# Screen.net
KiCad netlist of a schematic drawn in Altium Designer
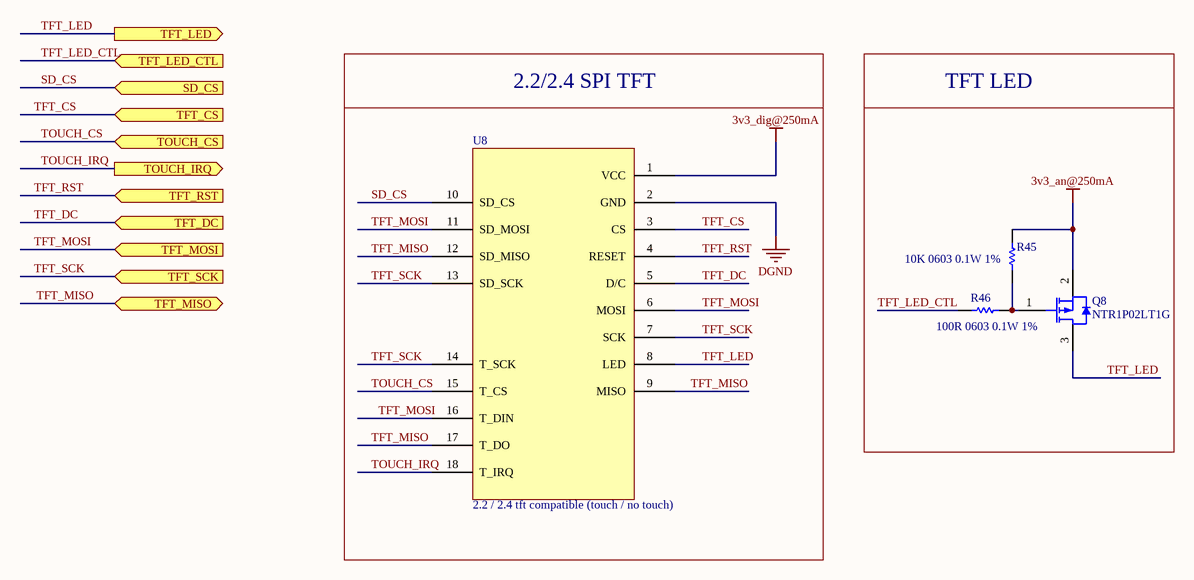
[diagram p0: Screen.SchDoc]

(export (version "E")
  (design (tool "Eeschema 10.0.6"))
  (components
    (comp (ref "Q8")
      (value "NTR1P02LT1G")
      (footprint "ONSC-SOT-23-3-318-08_V")
      (description "Power MOSFET, -20 V, -1.3 A, P-Channel, 3-Pin SOT-23, Pb-Free, Tape and Reel")
      (libsource (lib "CommunityVault") (part "ONSC-PMOS-G1S2D3-3_D"))
    )
    (comp (ref "R45")
      (value "10K 0603 0.1W 1%")
      (footprint "RESC1609X55X30ML10T20")
      (description "30K 0603 0.1W 1%")
      (fields (field (name "TOLERANCE") "1%"))
      (libsource (lib "CommunityVault") (part "CMP-4716590-9"))
    )
    (comp (ref "R46")
      (value "100R 0603 0.1W 1%")
      (footprint "RESC1609X55X30ML10T20")
      (fields (field (name "MANUFACTURER PART NUMBER") "CR0603-FX-1001ELF"))
      (libsource (lib "CommunityVault") (part "CMP-a61f6f36030f79d8-4"))
    )
    (comp (ref "U8")
      (value "2.2 / 2.4 tft compatible (touch / no touch)")
      (footprint "PCB-0iq7iyy8nrzrpmpo9lhg-1")
      (description "TZT 2.4\" 240x320 SPI TFT LCD Serial Port Module+5V/3.3V PBC Adapter Micro SD ILI9341")
      (libsource (lib "FavoritesLibrary") (part "SYM-m0xp0jkbbaqlzhag27re-1"))
    )
  )
  (nets
    (net (code "1") (name "/SD_CS") (class "Default")
      (node (ref "U8") (pin "10") (pinfunction "SD_CS_10") (pintype "passive"))
    )
    (net (code "2") (name "/TFT_CS") (class "Default")
      (node (ref "U8") (pin "3") (pinfunction "CS_3") (pintype "passive"))
    )
    (net (code "3") (name "/TFT_DC") (class "Default")
      (node (ref "U8") (pin "5") (pinfunction "D/C_5") (pintype "passive"))
    )
    (net (code "4") (name "/TFT_LED") (class "Default")
      (node (ref "Q8") (pin "3") (pinfunction "D_3") (pintype "passive"))
      (node (ref "U8") (pin "8") (pinfunction "LED_8") (pintype "passive"))
    )
    (net (code "5") (name "/TFT_LED_CTL") (class "Default")
      (node (ref "R46") (pin "2") (pinfunction "2_2") (pintype "passive"))
    )
    (net (code "6") (name "/TFT_MISO") (class "Default")
      (node (ref "U8") (pin "12") (pinfunction "SD_MISO_12") (pintype "passive"))
      (node (ref "U8") (pin "17") (pinfunction "T_DO_17") (pintype "passive"))
      (node (ref "U8") (pin "9") (pinfunction "MISO_9") (pintype "passive"))
    )
    (net (code "7") (name "/TFT_MOSI") (class "Default")
      (node (ref "U8") (pin "11") (pinfunction "SD_MOSI_11") (pintype "passive"))
      (node (ref "U8") (pin "16") (pinfunction "T_DIN_16") (pintype "passive"))
      (node (ref "U8") (pin "6") (pinfunction "MOSI_6") (pintype "passive"))
    )
    (net (code "8") (name "/TFT_RST") (class "Default")
      (node (ref "U8") (pin "4") (pinfunction "RESET_4") (pintype "passive"))
    )
    (net (code "9") (name "/TFT_SCK") (class "Default")
      (node (ref "U8") (pin "13") (pinfunction "SD_SCK_13") (pintype "passive"))
      (node (ref "U8") (pin "14") (pinfunction "T_SCK_14") (pintype "passive"))
      (node (ref "U8") (pin "7") (pinfunction "SCK_7") (pintype "passive"))
    )
    (net (code "10") (name "/TOUCH_CS") (class "Default")
      (node (ref "U8") (pin "15") (pinfunction "T_CS_15") (pintype "passive"))
    )
    (net (code "11") (name "/TOUCH_IRQ") (class "Default")
      (node (ref "U8") (pin "18") (pinfunction "T_IRQ_18") (pintype "passive"))
    )
    (net (code "12") (name "3v3_an@250mA") (class "Default")
      (node (ref "Q8") (pin "2") (pinfunction "S_2") (pintype "passive"))
      (node (ref "R45") (pin "2") (pinfunction "2_2") (pintype "passive"))
    )
    (net (code "13") (name "3v3_dig@250mA") (class "Default")
      (node (ref "U8") (pin "1") (pinfunction "VCC_1") (pintype "passive"))
    )
    (net (code "14") (name "DGND") (class "Default")
      (node (ref "U8") (pin "2") (pinfunction "GND_2") (pintype "passive"))
    )
    (net (code "15") (name "Net-(Q8-G)") (class "Default")
      (node (ref "Q8") (pin "1") (pinfunction "G_1") (pintype "passive"))
      (node (ref "R45") (pin "1") (pinfunction "1_1") (pintype "passive"))
      (node (ref "R46") (pin "1") (pinfunction "1_1") (pintype "passive"))
    )
  )
)
